# Power.net
KiCad netlist of a schematic drawn in Altium Designer
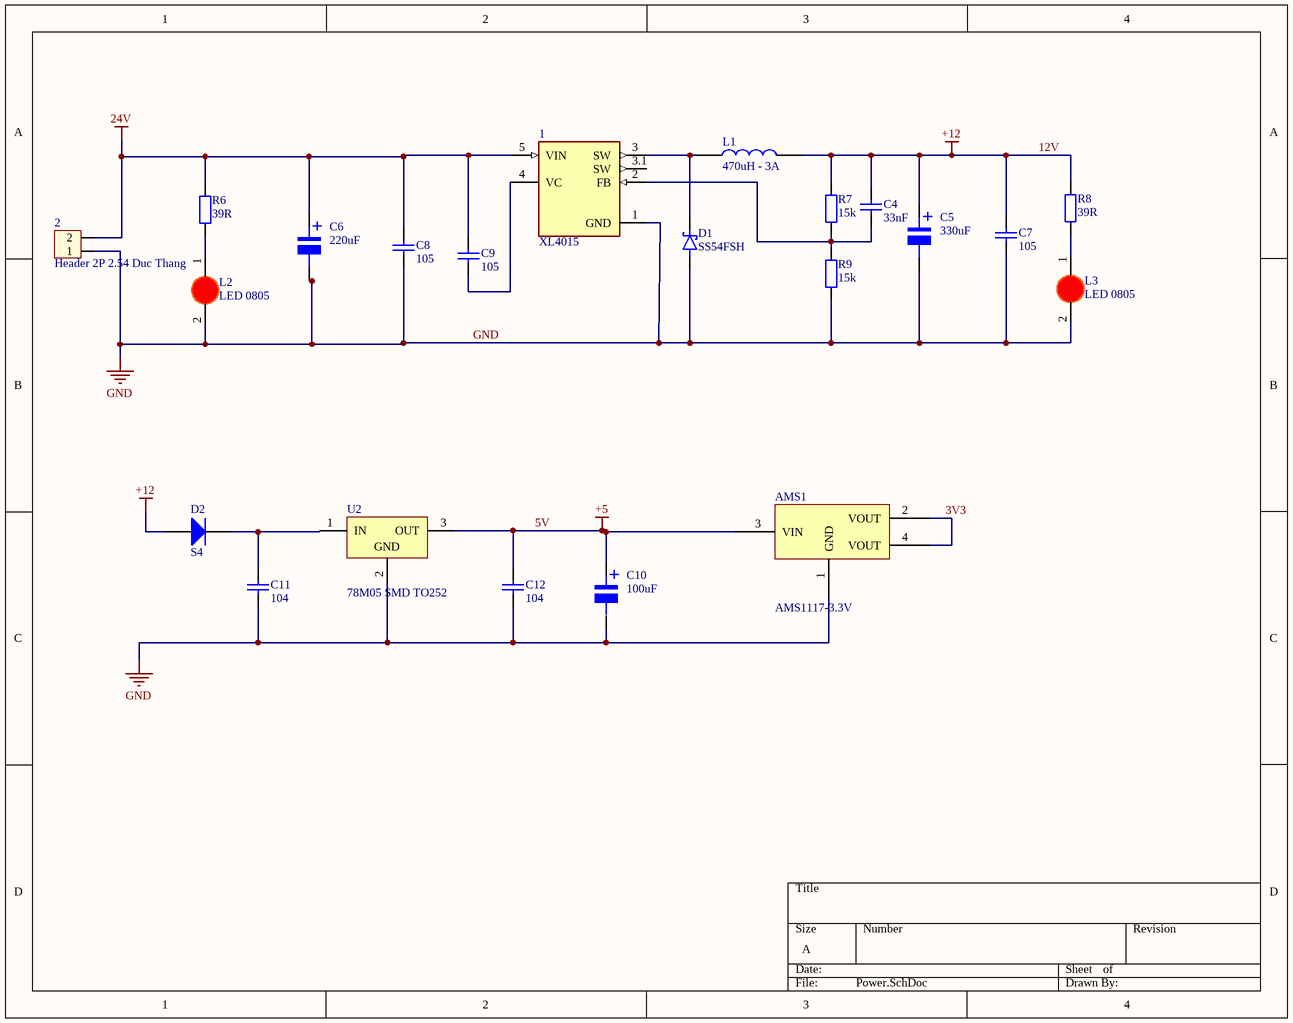
[diagram p0: Power.SchDoc]

(export (version "E")
  (design (tool "Eeschema 10.0.6"))
  (components
    (comp (ref "1")
      (value "XL4015")
      (footprint "CONV_XL4015")
      (description "5A 180KHz 36V Buck DC to DC Converter")
      (libsource (lib "XL4015") (part "XL4015"))
    )
    (comp (ref "2")
      (value "Header 2P 2.54 Duc Thang")
      (footprint "KF2-5.08")
      (description "Cắm")
      (libsource (lib "Altium_Lib_by_KhueNguyenCreator") (part "Header 2P 2.54 Duc Thang"))
    )
    (comp (ref "AMS1")
      (value "AMS1117-3.3V")
      (footprint "SOT223")
      (description "Dán")
      (libsource (lib "Altium_Lib_by_KhueNguyenCreator") (part "AMS1117 SMD"))
    )
    (comp (ref "C4")
      (value "33nF")
      (footprint "tu 0402")
      (description "Dán")
      (libsource (lib "Altium_Lib_by_KhueNguyenCreator") (part "Tu 0402 33nF 10V"))
    )
    (comp (ref "C5")
      (value "330uF")
      (footprint "tu nhom 10 (g)")
      (description "Dán")
      (libsource (lib "Altium_Lib_by_KhueNguyenCreator") (part "Tu Nhom 330uF 50V"))
    )
    (comp (ref "C6")
      (value "220uF")
      (footprint "tu nhom 10 (g)")
      (description "Dán")
      (libsource (lib "Altium_Lib_by_KhueNguyenCreator") (part "Tu Nhom 220uF 50V"))
    )
    (comp (ref "C7")
      (value "105")
      (footprint "tu 0603")
      (description "Dán")
      (libsource (lib "Altium_Lib_by_KhueNguyenCreator") (part "Tu 0603 105 16V 20%"))
    )
    (comp (ref "C8")
      (value "105")
      (footprint "tu 0603")
      (description "Dán")
      (libsource (lib "Altium_Lib_by_KhueNguyenCreator") (part "Tu 0603 105 50V 10%"))
    )
    (comp (ref "C9")
      (value "105")
      (footprint "tu 0603")
      (description "Dán")
      (libsource (lib "Altium_Lib_by_KhueNguyenCreator") (part "Tu 0603 105 50V 10%"))
    )
    (comp (ref "C10")
      (value "100uF")
      (footprint "tu nhom 6.3 (d)")
      (description "Dán")
      (libsource (lib "Altium_Lib_by_KhueNguyenCreator") (part "Tu Nhom 100uF 25V"))
    )
    (comp (ref "C11")
      (value "104")
      (footprint "tu 1206")
      (description "Dán")
      (libsource (lib "Altium_Lib_by_KhueNguyenCreator") (part "Tu 1206 104 50V 20%"))
    )
    (comp (ref "C12")
      (value "104")
      (footprint "tu 1206")
      (description "Dán")
      (libsource (lib "Altium_Lib_by_KhueNguyenCreator") (part "Tu 1206 104 50V 20%"))
    )
    (comp (ref "D1")
      (value "SS54FSH")
      (footprint "SODFL4725X110N")
      (description "5A, 40V, Schottky Rectifier")
      (fields (field (name "MF") "Taiwan Semiconductor"))
      (libsource (lib "SS54FSH") (part "SS54FSH"))
    )
    (comp (ref "D2")
      (value "S4")
      (footprint "DIODE SOD-123")
      (description "Dán")
      (libsource (lib "Altium_Lib_by_KhueNguyenCreator") (part "Diode S4"))
    )
    (comp (ref "L1")
      (value "470uH - 3A")
      (footprint "CUON CAM 100uH3A")
      (description "Cắm")
      (libsource (lib "Altium_Lib_by_KhueNguyenCreator") (part "CUON CAM 470uH DIP"))
    )
    (comp (ref "L2")
      (value "LED 0805")
      (footprint "LED-0805-Red")
      (description "Dán")
      (libsource (lib "Altium_Lib_by_KhueNguyenCreator") (part "LED 0805 Do"))
    )
    (comp (ref "L3")
      (value "LED 0805")
      (footprint "LED-0805-Red")
      (description "Dán")
      (libsource (lib "Altium_Lib_by_KhueNguyenCreator") (part "LED 0805 Do"))
    )
    (comp (ref "R6")
      (value "39R")
      (footprint "tro smd 0603")
      (description "Dán")
      (libsource (lib "Altium_Lib_by_KhueNguyenCreator") (part "Tro 0603 5% 39R"))
    )
    (comp (ref "R7")
      (value "15k")
      (footprint "tro smd 0603")
      (description "Dán")
      (libsource (lib "Altium_Lib_by_KhueNguyenCreator") (part "Tro 0603 5% 15k"))
    )
    (comp (ref "R8")
      (value "39R")
      (footprint "tro smd 0603")
      (description "Dán")
      (libsource (lib "Altium_Lib_by_KhueNguyenCreator") (part "Tro 0603 5% 39R"))
    )
    (comp (ref "R9")
      (value "15k")
      (footprint "tro smd 0603")
      (description "Dán")
      (libsource (lib "Altium_Lib_by_KhueNguyenCreator") (part "Tro 0603 5% 15k"))
    )
    (comp (ref "U2")
      (value "78M05 SMD TO252")
      (footprint "TO252")
      (description "Dán")
      (libsource (lib "Altium_Lib_by_KhueNguyenCreator") (part "78M05 SMD TO252"))
    )
  )
  (nets
    (net (code "1") (name "+5") (class "Default")
      (node (ref "AMS1") (pin "3") (pinfunction "VIN_3") (pintype "passive"))
      (node (ref "C10") (pin "1") (pinfunction "1_1") (pintype "passive"))
      (node (ref "C12") (pin "1") (pinfunction "1_1") (pintype "passive"))
      (node (ref "U2") (pin "3") (pinfunction "OUT_3") (pintype "power_in"))
    )
    (net (code "2") (name "+12") (class "Default")
      (node (ref "C4") (pin "1") (pinfunction "1_1") (pintype "passive"))
      (node (ref "C5") (pin "1") (pinfunction "1_1") (pintype "passive"))
      (node (ref "C7") (pin "1") (pinfunction "1_1") (pintype "passive"))
      (node (ref "D2") (pin "1") (pinfunction "A_1") (pintype "passive"))
      (node (ref "L1") (pin "2") (pinfunction "2_2") (pintype "passive"))
      (node (ref "R7") (pin "2") (pinfunction "2_2") (pintype "passive"))
      (node (ref "R8") (pin "2") (pinfunction "2_2") (pintype "passive"))
    )
    (net (code "3") (name "/3V3") (class "Default")
      (node (ref "AMS1") (pin "2") (pinfunction "VOUT_2") (pintype "passive"))
      (node (ref "AMS1") (pin "4") (pinfunction "VOUT_4") (pintype "passive"))
    )
    (net (code "4") (name "24V") (class "Default")
      (node (ref "1") (pin "5") (pinfunction "VIN_5") (pintype "input"))
      (node (ref "2") (pin "2") (pinfunction "2_2") (pintype "passive"))
      (node (ref "C6") (pin "1") (pinfunction "1_1") (pintype "passive"))
      (node (ref "C8") (pin "2") (pinfunction "2_2") (pintype "passive"))
      (node (ref "C9") (pin "2") (pinfunction "2_2") (pintype "passive"))
      (node (ref "R6") (pin "2") (pinfunction "2_2") (pintype "passive"))
    )
    (net (code "5") (name "GND") (class "Default")
      (node (ref "1") (pin "1") (pinfunction "GND_1") (pintype "power_in"))
      (node (ref "2") (pin "1") (pinfunction "1_1") (pintype "passive"))
      (node (ref "AMS1") (pin "1") (pinfunction "GND_1") (pintype "passive"))
      (node (ref "C10") (pin "2") (pinfunction "2_2") (pintype "passive"))
      (node (ref "C11") (pin "2") (pinfunction "2_2") (pintype "passive"))
      (node (ref "C12") (pin "2") (pinfunction "2_2") (pintype "passive"))
      (node (ref "C5") (pin "2") (pinfunction "2_2") (pintype "passive"))
      (node (ref "C6") (pin "2") (pinfunction "2_2") (pintype "passive"))
      (node (ref "C7") (pin "2") (pinfunction "2_2") (pintype "passive"))
      (node (ref "C8") (pin "1") (pinfunction "1_1") (pintype "passive"))
      (node (ref "D1") (pin "A") (pinfunction "A_A") (pintype "passive"))
      (node (ref "L2") (pin "2") (pinfunction "K_2") (pintype "passive"))
      (node (ref "L3") (pin "2") (pinfunction "K_2") (pintype "passive"))
      (node (ref "R9") (pin "1") (pinfunction "1_1") (pintype "passive"))
      (node (ref "U2") (pin "2") (pinfunction "GND_2") (pintype "power_in"))
    )
    (net (code "6") (name "Net-(1-FB)") (class "Default")
      (node (ref "1") (pin "2") (pinfunction "FB_2") (pintype "input"))
      (node (ref "C4") (pin "2") (pinfunction "2_2") (pintype "passive"))
      (node (ref "R7") (pin "1") (pinfunction "1_1") (pintype "passive"))
      (node (ref "R9") (pin "2") (pinfunction "2_2") (pintype "passive"))
    )
    (net (code "7") (name "Net-(1-VC)") (class "Default")
      (node (ref "1") (pin "4") (pinfunction "VC_4") (pintype "passive"))
      (node (ref "C9") (pin "1") (pinfunction "1_1") (pintype "passive"))
    )
    (net (code "8") (name "Net-(D1-K)") (class "Default")
      (node (ref "1") (pin "3") (pinfunction "SW_3") (pintype "output"))
      (node (ref "D1") (pin "C") (pinfunction "K_C") (pintype "passive"))
      (node (ref "L1") (pin "1") (pinfunction "1_1") (pintype "passive"))
    )
    (net (code "9") (name "Net-(D2-K)") (class "Default")
      (node (ref "C11") (pin "1") (pinfunction "1_1") (pintype "passive"))
      (node (ref "D2") (pin "2") (pinfunction "K_2") (pintype "passive"))
      (node (ref "U2") (pin "1") (pinfunction "IN_1") (pintype "power_in"))
    )
    (net (code "10") (name "Net-(L2-A)") (class "Default")
      (node (ref "L2") (pin "1") (pinfunction "A_1") (pintype "passive"))
      (node (ref "R6") (pin "1") (pinfunction "1_1") (pintype "passive"))
    )
    (net (code "11") (name "Net-(L3-A)") (class "Default")
      (node (ref "L3") (pin "1") (pinfunction "A_1") (pintype "passive"))
      (node (ref "R8") (pin "1") (pinfunction "1_1") (pintype "passive"))
    )
    (net (code "12") (name "unconnected-(1-SW-Pad3.1)") (class "Default")
      (node (ref "1") (pin "3.1") (pinfunction "SW_3.1") (pintype "output"))
    )
  )
)
